# Power.net
KiCad netlist of a schematic drawn in Altium Designer
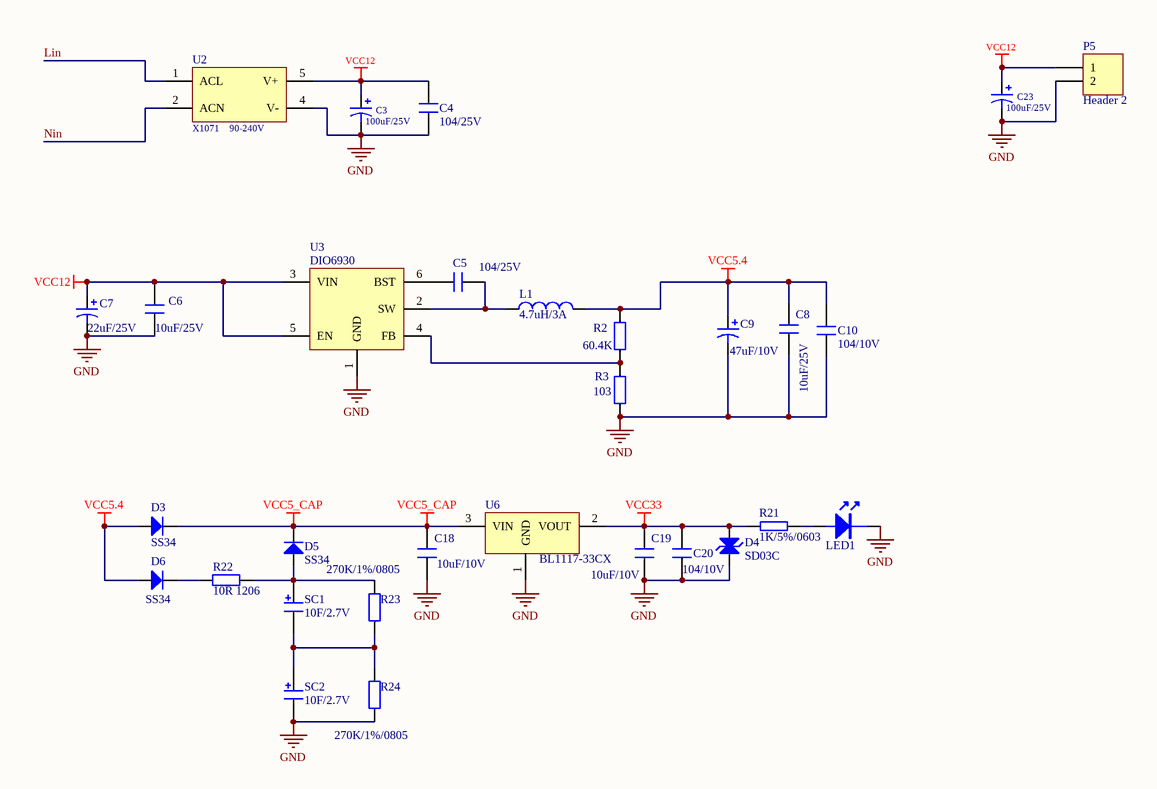
[diagram p0: Power.SchDoc]

(export (version "E")
  (design (tool "Eeschema 10.0.6"))
  (components
    (comp (ref "C3")
      (value "100uF/25V")
      (footprint "CAPPIND06")
      (description "Polarized Capacitor (Radial)")
      (fields (field (name "PUBLISHER") "Altium Limited"))
      (libsource (lib "Miscellaneous Devices") (part "Cap Pol1"))
    )
    (comp (ref "C4") (value "104/25V") (footprint "0603R") (libsource (lib "ES_Schematic") (part "CAP_1")))
    (comp (ref "C5") (value "104/25V") (footprint "0603R") (libsource (lib "ES_Schematic") (part "CAP_1")))
    (comp (ref "C6") (value "10uF/25V") (footprint "0603R") (libsource (lib "ES_Schematic") (part "CAP")))
    (comp (ref "C7")
      (value "22uF/25V")
      (footprint "0805R")
      (description "Polarized Capacitor (Radial)")
      (fields (field (name "PUBLISHER") "Altium Limited"))
      (libsource (lib "Miscellaneous Devices") (part "Cap Pol1"))
    )
    (comp (ref "C8") (value "10uF/25V") (footprint "0603R") (libsource (lib "ES_Schematic") (part "CAP")))
    (comp (ref "C9")
      (value "47uF/10V")
      (footprint "0805R")
      (description "Polarized Capacitor (Radial)")
      (fields (field (name "PUBLISHER") "Altium Limited"))
      (libsource (lib "Miscellaneous Devices") (part "Cap Pol1"))
    )
    (comp (ref "C10") (value "104/10V") (footprint "0603R") (libsource (lib "ES_Schematic") (part "CAP_1")))
    (comp (ref "C18") (value "10uF/10V") (footprint "0603R") (libsource (lib "ES_Schematic") (part "CAP")))
    (comp (ref "C19") (value "10uF/10V") (footprint "0603R") (libsource (lib "ES_Schematic") (part "CAP")))
    (comp (ref "C20") (value "104/10V") (footprint "0603R") (libsource (lib "ES_Schematic") (part "CAP_1")))
    (comp (ref "C23")
      (value "100uF/25V")
      (footprint "CAPPIND06")
      (description "Polarized Capacitor (Radial)")
      (fields (field (name "PUBLISHER") "Altium Limited"))
      (libsource (lib "Miscellaneous Devices") (part "Cap Pol1"))
    )
    (comp (ref "D3") (value "SS34") (footprint "DO-214AC") (libsource (lib "ES_Schematic") (part "DIODE")))
    (comp (ref "D4") (value "SD03C") (footprint "SOD323") (libsource (lib "ES_Schematic") (part "TVS")))
    (comp (ref "D5") (value "SS34") (footprint "DO-214AC") (libsource (lib "ES_Schematic") (part "DIODE")))
    (comp (ref "D6") (value "SS34") (footprint "DO-214AC") (libsource (lib "ES_Schematic") (part "DIODE")))
    (comp (ref "L1")
      (value "4.7uH/3A")
      (footprint "贴片电感5020")
      (description "Inductor")
      (fields (field (name "PUBLISHER") "Altium Limited"))
      (libsource (lib "Miscellaneous Devices") (part "Inductor"))
    )
    (comp (ref "LED1") (value "LED") (footprint "0603LED") (libsource (lib "ES_Schematic") (part "LED")))
    (comp (ref "P5")
      (value "Header 2")
      (footprint "CONN-TH_P5.08_KF127-5.08-2P")
      (description "Header, 2-Pin")
      (fields (field (name "PUBLISHER") "Altium Limited"))
      (libsource (lib "Miscellaneous Connectors") (part "Header 2"))
    )
    (comp (ref "R2")
      (value "60.4K")
      (footprint "0603R")
      (description "Resistor")
      (fields (field (name "PUBLISHER") "Altium Limited"))
      (libsource (lib "") (part "Res2_1"))
    )
    (comp (ref "R3")
      (value "103")
      (footprint "0603R")
      (description "Resistor")
      (fields (field (name "PUBLISHER") "Altium Limited"))
      (libsource (lib "") (part "Res2_1"))
    )
    (comp (ref "R21") (value "1K/5%/0603") (footprint "0603R") (libsource (lib "ES_Schematic") (part "RES")))
    (comp (ref "R22")
      (value "10R 1206")
      (footprint "1206")
      (description "Resistor")
      (fields (field (name "PUBLISHER") "Altium Limited"))
      (libsource (lib "") (part "Res2_2"))
    )
    (comp (ref "R23")
      (value "270K/1%/0805")
      (footprint "0805R")
      (description "Resistor")
      (fields (field (name "PUBLISHER") "Altium Limited"))
      (libsource (lib "Miscellaneous Devices") (part "Res2"))
    )
    (comp (ref "R24")
      (value "270K/1%/0805")
      (footprint "0805R")
      (description "Resistor")
      (fields (field (name "PUBLISHER") "Altium Limited"))
      (libsource (lib "Miscellaneous Devices") (part "Res2"))
    )
    (comp (ref "SC1")
      (value "10F/2.7V")
      (footprint "SuperCap-12.5*20 - 躺着")
      (libsource (lib "ES_Schematic") (part "CAP+"))
    )
    (comp (ref "SC2")
      (value "10F/2.7V")
      (footprint "SuperCap-12.5*20 - 躺着")
      (libsource (lib "ES_Schematic") (part "CAP+"))
    )
    (comp (ref "U2")
      (value "X1071    90-240V")
      (footprint "X1071")
      (libsource (lib "sangjian") (part "AD2DC_EMC"))
    )
    (comp (ref "U3")
      (value "DIO6930")
      (footprint "SOT-23-6DBV")
      (libsource (lib "ES_Schematic") (part "BL8032"))
    )
    (comp (ref "U6")
      (value "BL1117-33CX")
      (footprint "SOT-223")
      (libsource (lib "ES_Schematic") (part "AMS1117"))
    )
  )
  (nets
    (net (code "1") (name "/Lin") (class "Default")
      (node (ref "U2") (pin "1") (pinfunction "ACL_1") (pintype "passive"))
    )
    (net (code "2") (name "/Nin") (class "Default")
      (node (ref "U2") (pin "2") (pinfunction "ACN_2") (pintype "passive"))
    )
    (net (code "3") (name "GND") (class "Default")
      (node (ref "C10") (pin "1") (pinfunction "1_1") (pintype "passive"))
      (node (ref "C18") (pin "1") (pinfunction "1_1") (pintype "passive"))
      (node (ref "C19") (pin "1") (pinfunction "1_1") (pintype "passive"))
      (node (ref "C20") (pin "1") (pinfunction "1_1") (pintype "passive"))
      (node (ref "C23") (pin "2") (pinfunction "2_2") (pintype "passive"))
      (node (ref "C3") (pin "2") (pinfunction "2_2") (pintype "passive"))
      (node (ref "C4") (pin "1") (pinfunction "1_1") (pintype "passive"))
      (node (ref "C6") (pin "1") (pinfunction "1_1") (pintype "passive"))
      (node (ref "C7") (pin "2") (pinfunction "2_2") (pintype "passive"))
      (node (ref "C8") (pin "1") (pinfunction "1_1") (pintype "passive"))
      (node (ref "C9") (pin "2") (pinfunction "2_2") (pintype "passive"))
      (node (ref "D4") (pin "2") (pinfunction "A_2") (pintype "passive"))
      (node (ref "LED1") (pin "2") (pinfunction "2_2") (pintype "passive"))
      (node (ref "P5") (pin "2") (pinfunction "2_2") (pintype "passive"))
      (node (ref "R24") (pin "1") (pinfunction "1_1") (pintype "passive"))
      (node (ref "R3") (pin "2") (pinfunction "2_2") (pintype "passive"))
      (node (ref "SC2") (pin "2") (pinfunction "2_2") (pintype "passive"))
      (node (ref "U2") (pin "4") (pinfunction "V-_4") (pintype "passive"))
      (node (ref "U3") (pin "1") (pinfunction "GND_1") (pintype "passive"))
      (node (ref "U6") (pin "1") (pinfunction "GND_1") (pintype "passive"))
    )
    (net (code "4") (name "Net-(D5-A)") (class "Default")
      (node (ref "D5") (pin "2") (pinfunction "A_2") (pintype "passive"))
      (node (ref "R22") (pin "1") (pinfunction "1_1") (pintype "passive"))
      (node (ref "R23") (pin "2") (pinfunction "2_2") (pintype "passive"))
      (node (ref "SC1") (pin "1") (pinfunction "1_1") (pintype "passive"))
    )
    (net (code "5") (name "Net-(D6-K)") (class "Default")
      (node (ref "D6") (pin "1") (pinfunction "K_1") (pintype "passive"))
      (node (ref "R22") (pin "2") (pinfunction "2_2") (pintype "passive"))
    )
    (net (code "6") (name "Net-(LED1-Pad1)") (class "Default")
      (node (ref "LED1") (pin "1") (pinfunction "1_1") (pintype "passive"))
      (node (ref "R21") (pin "2") (pinfunction "2_2") (pintype "passive"))
    )
    (net (code "7") (name "Net-(R23-Pad1)") (class "Default")
      (node (ref "R23") (pin "1") (pinfunction "1_1") (pintype "passive"))
      (node (ref "R24") (pin "2") (pinfunction "2_2") (pintype "passive"))
      (node (ref "SC1") (pin "2") (pinfunction "2_2") (pintype "passive"))
      (node (ref "SC2") (pin "1") (pinfunction "1_1") (pintype "passive"))
    )
    (net (code "8") (name "Net-(U3-BST)") (class "Default")
      (node (ref "C5") (pin "2") (pinfunction "2_2") (pintype "passive"))
      (node (ref "U3") (pin "6") (pinfunction "BST_6") (pintype "passive"))
    )
    (net (code "9") (name "Net-(U3-FB)") (class "Default")
      (node (ref "R2") (pin "2") (pinfunction "2_2") (pintype "passive"))
      (node (ref "R3") (pin "1") (pinfunction "1_1") (pintype "passive"))
      (node (ref "U3") (pin "4") (pinfunction "FB_4") (pintype "passive"))
    )
    (net (code "10") (name "Net-(U3-SW)") (class "Default")
      (node (ref "C5") (pin "1") (pinfunction "1_1") (pintype "passive"))
      (node (ref "L1") (pin "1") (pinfunction "1_1") (pintype "passive"))
      (node (ref "U3") (pin "2") (pinfunction "SW_2") (pintype "passive"))
    )
    (net (code "11") (name "VCC5.4") (class "Default")
      (node (ref "C10") (pin "2") (pinfunction "2_2") (pintype "passive"))
      (node (ref "C8") (pin "2") (pinfunction "2_2") (pintype "passive"))
      (node (ref "C9") (pin "1") (pinfunction "1_1") (pintype "passive"))
      (node (ref "D3") (pin "2") (pinfunction "A_2") (pintype "passive"))
      (node (ref "D6") (pin "2") (pinfunction "A_2") (pintype "passive"))
      (node (ref "L1") (pin "2") (pinfunction "2_2") (pintype "passive"))
      (node (ref "R2") (pin "1") (pinfunction "1_1") (pintype "passive"))
    )
    (net (code "12") (name "VCC5_CAP") (class "Default")
      (node (ref "C18") (pin "2") (pinfunction "2_2") (pintype "passive"))
      (node (ref "D3") (pin "1") (pinfunction "K_1") (pintype "passive"))
      (node (ref "D5") (pin "1") (pinfunction "K_1") (pintype "passive"))
      (node (ref "U6") (pin "3") (pinfunction "VIN_3") (pintype "passive"))
    )
    (net (code "13") (name "VCC12") (class "Default")
      (node (ref "C23") (pin "1") (pinfunction "1_1") (pintype "passive"))
      (node (ref "C3") (pin "1") (pinfunction "1_1") (pintype "passive"))
      (node (ref "C4") (pin "2") (pinfunction "2_2") (pintype "passive"))
      (node (ref "C6") (pin "2") (pinfunction "2_2") (pintype "passive"))
      (node (ref "C7") (pin "1") (pinfunction "1_1") (pintype "passive"))
      (node (ref "P5") (pin "1") (pinfunction "1_1") (pintype "passive"))
      (node (ref "U2") (pin "5") (pinfunction "V+_5") (pintype "passive"))
      (node (ref "U3") (pin "3") (pinfunction "VIN_3") (pintype "passive"))
      (node (ref "U3") (pin "5") (pinfunction "EN_5") (pintype "passive"))
    )
    (net (code "14") (name "VCC33") (class "Default")
      (node (ref "C19") (pin "2") (pinfunction "2_2") (pintype "passive"))
      (node (ref "C20") (pin "2") (pinfunction "2_2") (pintype "passive"))
      (node (ref "D4") (pin "1") (pinfunction "K_1") (pintype "passive"))
      (node (ref "R21") (pin "1") (pinfunction "1_1") (pintype "passive"))
      (node (ref "U6") (pin "2") (pinfunction "VOUT_2") (pintype "passive"))
    )
  )
)
